# MCU_RTC_DIAGRAM_REV_2_0.net
KiCad netlist of a schematic drawn in EAGLE
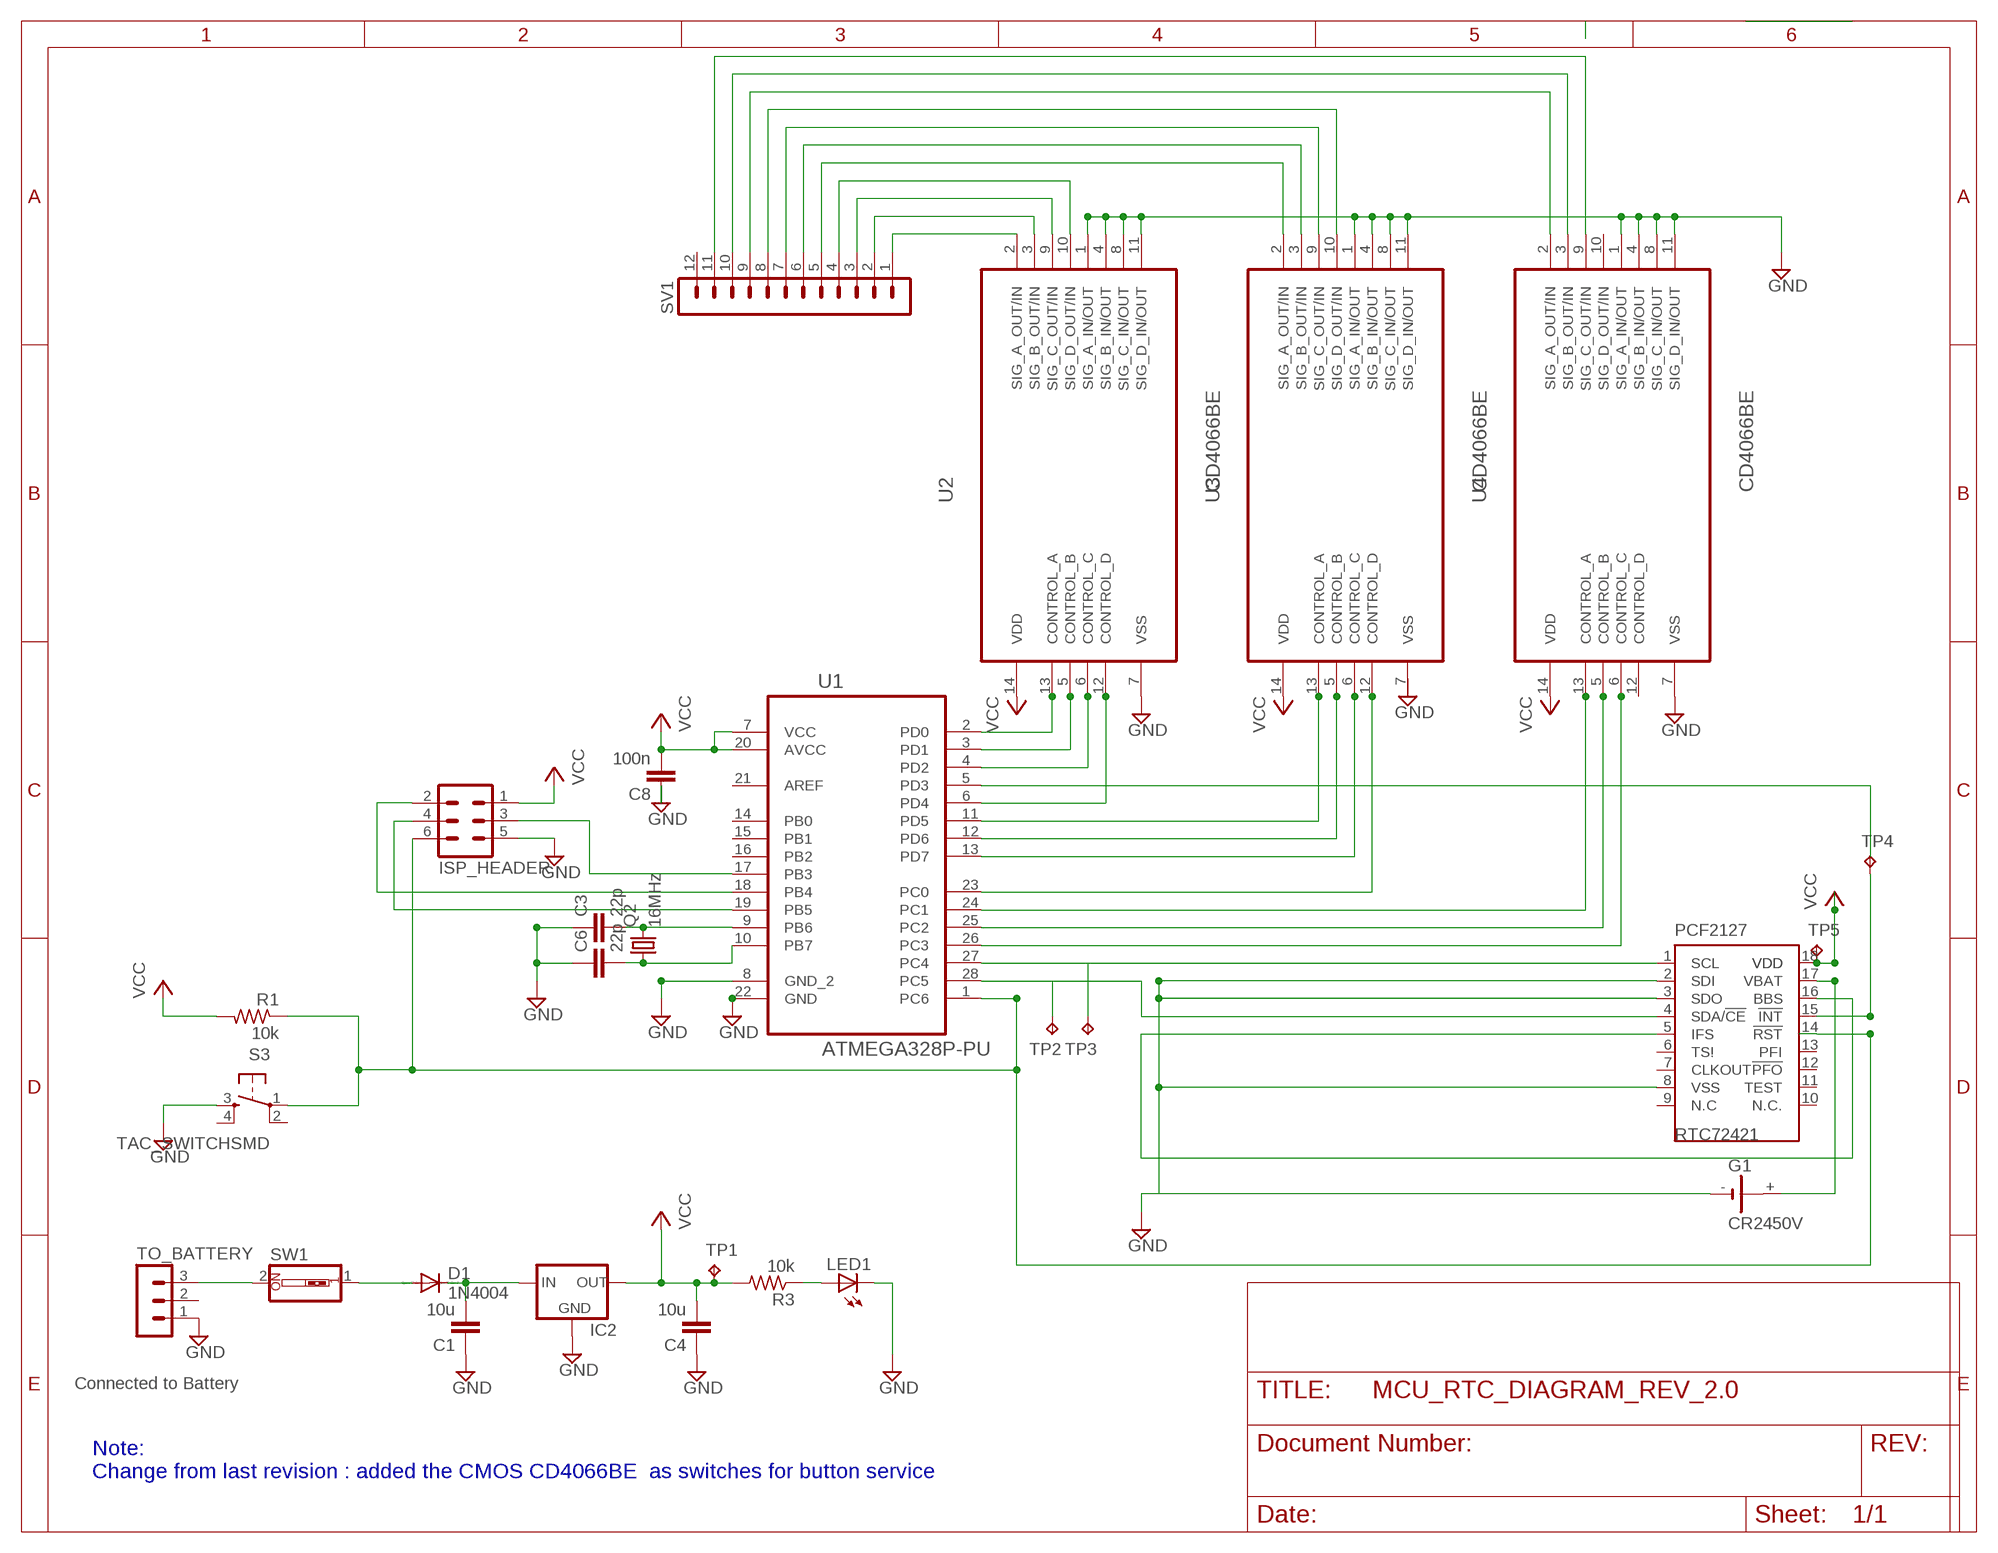
[diagram p0: schematic, sheet 1]

(export (version "E")
  (design (tool "Eeschema 10.0.6"))
  (components
    (comp (ref "C1")
      (value "10u")
      (footprint "eagle-import:C0805")
      (libsource (lib "eagle-import") (part "C-EUC0805"))
    )
    (comp (ref "C3")
      (value "22p")
      (footprint "eagle-import:C0805")
      (libsource (lib "eagle-import") (part "C-EUC0805"))
    )
    (comp (ref "C4")
      (value "10u")
      (footprint "eagle-import:C0805")
      (libsource (lib "eagle-import") (part "C-EUC0805"))
    )
    (comp (ref "C6")
      (value "22p")
      (footprint "eagle-import:C0805")
      (libsource (lib "eagle-import") (part "C-EUC0805"))
    )
    (comp (ref "C8")
      (value "100n")
      (footprint "eagle-import:C0805")
      (libsource (lib "eagle-import") (part "C-EUC0805"))
    )
    (comp (ref "D1")
      (value "1N4004")
      (footprint "eagle-import:DO41-10")
      (libsource (lib "eagle-import") (part "1N4004"))
    )
    (comp (ref "G1")
      (value "CR2450V")
      (footprint "eagle-import:CR2450V")
      (libsource (lib "eagle-import") (part "CR2450V"))
    )
    (comp (ref "IC1")
      (value "RTC72421")
      (footprint "eagle-import:DIL18")
      (fields (field (name "MPN") "RTC72421B"))
      (libsource (lib "eagle-import") (part "RTC72421"))
    )
    (comp (ref "IC2")
      (value "78XXL")
      (footprint "eagle-import:78XXL")
      (libsource (lib "eagle-import") (part "78XXL"))
    )
    (comp (ref "ISP_HEADER")
      (value "MA03-2")
      (footprint "eagle-import:MA03-2")
      (libsource (lib "eagle-import") (part "MA03-2"))
    )
    (comp (ref "LED1")
      (value "LEDCHIPLED_0805")
      (footprint "eagle-import:CHIPLED_0805")
      (libsource (lib "eagle-import") (part "LEDCHIPLED_0805"))
    )
    (comp (ref "Q2")
      (value "16MHz")
      (footprint "eagle-import:HC49_S")
      (libsource (lib "eagle-import") (part "CRYSTALHC49S"))
    )
    (comp (ref "R1")
      (value "10k")
      (footprint "eagle-import:R0805")
      (libsource (lib "eagle-import") (part "R-US_R0805"))
    )
    (comp (ref "R3")
      (value "10k")
      (footprint "eagle-import:R0805")
      (libsource (lib "eagle-import") (part "R-US_R0805"))
    )
    (comp (ref "S3")
      (value "TAC_SWITCHSMD")
      (footprint "eagle-import:TACTILE-SWITCH-SMD")
      (libsource (lib "eagle-import") (part "TAC_SWITCHSMD"))
    )
    (comp (ref "SV1")
      (value "MA12-1W")
      (footprint "eagle-import:MA12-1W")
      (libsource (lib "eagle-import") (part "MA12-1W"))
    )
    (comp (ref "SW1")
      (value "SW_DIP-1")
      (footprint "eagle-import:EDG-01")
      (libsource (lib "eagle-import") (part "SW_DIP-1"))
    )
    (comp (ref "TO_BATTERY")
      (value "MA03-1")
      (footprint "eagle-import:MA03-1")
      (libsource (lib "eagle-import") (part "MA03-1"))
    )
    (comp (ref "TP1")
      (value "TPB1,27")
      (footprint "eagle-import:B1,27")
      (libsource (lib "eagle-import") (part "TPB1,27"))
    )
    (comp (ref "TP2")
      (value "TPB1,27")
      (footprint "eagle-import:B1,27")
      (libsource (lib "eagle-import") (part "TPB1,27"))
    )
    (comp (ref "TP3")
      (value "TPB1,27")
      (footprint "eagle-import:B1,27")
      (libsource (lib "eagle-import") (part "TPB1,27"))
    )
    (comp (ref "TP4")
      (value "TPB1,27")
      (footprint "eagle-import:B1,27")
      (libsource (lib "eagle-import") (part "TPB1,27"))
    )
    (comp (ref "TP5")
      (value "TPB1,27")
      (footprint "eagle-import:B1,27")
      (libsource (lib "eagle-import") (part "TPB1,27"))
    )
    (comp (ref "U1")
      (value "ATMEGA328P-PU")
      (footprint "eagle-import:DIP254P762X457-28")
      (libsource (lib "eagle-import") (part "ATMEGA328P-PU"))
    )
    (comp (ref "U2")
      (value "CD4066BE")
      (footprint "eagle-import:DIP254P762X508-14")
      (libsource (lib "eagle-import") (part "CD4066BE"))
    )
    (comp (ref "U3")
      (value "CD4066BE")
      (footprint "eagle-import:DIP254P762X508-14")
      (libsource (lib "eagle-import") (part "CD4066BE"))
    )
    (comp (ref "U4")
      (value "CD4066BE")
      (footprint "eagle-import:DIP254P762X508-14")
      (libsource (lib "eagle-import") (part "CD4066BE"))
    )
  )
  (nets
    (net (code "1") (name "GND") (class "Default")
      (node (ref "C1") (pin "1") (pinfunction "1_1") (pintype "passive"))
      (node (ref "C3") (pin "1") (pinfunction "1_1") (pintype "passive"))
      (node (ref "C4") (pin "1") (pinfunction "1_1") (pintype "passive"))
      (node (ref "C6") (pin "1") (pinfunction "1_1") (pintype "passive"))
      (node (ref "C8") (pin "1") (pinfunction "1_1") (pintype "passive"))
      (node (ref "G1") (pin "-") (pinfunction "-_-") (pintype "passive"))
      (node (ref "IC1") (pin "2") (pinfunction "SDI_2") (pintype "input"))
      (node (ref "IC1") (pin "3") (pinfunction "SDO_3") (pintype "input"))
      (node (ref "IC1") (pin "8") (pinfunction "VSS_8") (pintype "input"))
      (node (ref "IC2") (pin "GND") (pinfunction "GND_GND") (pintype "input"))
      (node (ref "ISP_HEADER") (pin "5") (pinfunction "5_5") (pintype "passive"))
      (node (ref "LED1") (pin "C") (pinfunction "C_C") (pintype "passive"))
      (node (ref "S3") (pin "3") (pinfunction "3_3") (pintype "passive"))
      (node (ref "TO_BATTERY") (pin "1") (pinfunction "1_1") (pintype "passive"))
      (node (ref "U1") (pin "22") (pinfunction "GND_22") (pintype "passive"))
      (node (ref "U1") (pin "8") (pinfunction "GND_2_8") (pintype "passive"))
      (node (ref "U2") (pin "1") (pinfunction "SIG_A_IN/OUT_1") (pintype "bidirectional"))
      (node (ref "U2") (pin "11") (pinfunction "SIG_D_IN/OUT_11") (pintype "bidirectional"))
      (node (ref "U2") (pin "4") (pinfunction "SIG_B_IN/OUT_4") (pintype "bidirectional"))
      (node (ref "U2") (pin "7") (pinfunction "VSS_7") (pintype "passive"))
      (node (ref "U2") (pin "8") (pinfunction "SIG_C_IN/OUT_8") (pintype "bidirectional"))
      (node (ref "U3") (pin "1") (pinfunction "SIG_A_IN/OUT_1") (pintype "bidirectional"))
      (node (ref "U3") (pin "11") (pinfunction "SIG_D_IN/OUT_11") (pintype "bidirectional"))
      (node (ref "U3") (pin "4") (pinfunction "SIG_B_IN/OUT_4") (pintype "bidirectional"))
      (node (ref "U3") (pin "8") (pinfunction "SIG_C_IN/OUT_8") (pintype "bidirectional"))
      (node (ref "U4") (pin "1") (pinfunction "SIG_A_IN/OUT_1") (pintype "bidirectional"))
      (node (ref "U4") (pin "11") (pinfunction "SIG_D_IN/OUT_11") (pintype "bidirectional"))
      (node (ref "U4") (pin "4") (pinfunction "SIG_B_IN/OUT_4") (pintype "bidirectional"))
      (node (ref "U4") (pin "7") (pinfunction "VSS_7") (pintype "passive"))
      (node (ref "U4") (pin "8") (pinfunction "SIG_C_IN/OUT_8") (pintype "bidirectional"))
    )
    (net (code "2") (name "Net-(C1-Pad2)") (class "Default")
      (node (ref "C1") (pin "2") (pinfunction "2_2") (pintype "passive"))
      (node (ref "D1") (pin "C") (pinfunction "C_C") (pintype "passive"))
      (node (ref "IC2") (pin "IN") (pinfunction "IN_IN") (pintype "input"))
    )
    (net (code "3") (name "Net-(D1-PadA)") (class "Default")
      (node (ref "D1") (pin "A") (pinfunction "A_A") (pintype "passive"))
      (node (ref "SW1") (pin "1") (pinfunction "1_1") (pintype "passive"))
    )
    (net (code "4") (name "Net-(IC1-IFS)") (class "Default")
      (node (ref "IC1") (pin "16") (pinfunction "VCC_16") (pintype "power_in"))
      (node (ref "IC1") (pin "5") (pinfunction "IFS_5") (pintype "input"))
    )
    (net (code "5") (name "Net-(IC1-SCL)") (class "Default")
      (node (ref "IC1") (pin "1") (pinfunction "SCL_1") (pintype "input"))
      (node (ref "TP3") (pin "TP") (pinfunction "TP_TP") (pintype "input"))
      (node (ref "U1") (pin "27") (pinfunction "PC4_27") (pintype "bidirectional"))
    )
    (net (code "6") (name "Net-(IC1-SDA{slash}~{CE})") (class "Default")
      (node (ref "IC1") (pin "4") (pinfunction "SDA/~{CE}_4") (pintype "input"))
      (node (ref "TP2") (pin "TP") (pinfunction "TP_TP") (pintype "input"))
      (node (ref "U1") (pin "28") (pinfunction "PC5_28") (pintype "bidirectional"))
    )
    (net (code "7") (name "Net-(IC1-VBAT)") (class "Default")
      (node (ref "G1") (pin "+") (pinfunction "+_+") (pintype "passive"))
      (node (ref "IC1") (pin "17") (pinfunction "VBAT_17") (pintype "power_in"))
    )
    (net (code "8") (name "Net-(IC1-~{INT})") (class "Default")
      (node (ref "IC1") (pin "15") (pinfunction "~{INT}_15") (pintype "input"))
      (node (ref "TP4") (pin "TP") (pinfunction "TP_TP") (pintype "input"))
    )
    (net (code "9") (name "Net-(IC1-~{RST})") (class "Default")
      (node (ref "IC1") (pin "14") (pinfunction "~{RST}_14") (pintype "bidirectional"))
      (node (ref "ISP_HEADER") (pin "6") (pinfunction "6_6") (pintype "passive"))
      (node (ref "R1") (pin "1") (pinfunction "1_1") (pintype "passive"))
      (node (ref "S3") (pin "1") (pinfunction "1_1") (pintype "passive"))
      (node (ref "U1") (pin "1") (pinfunction "PC6_1") (pintype "bidirectional"))
    )
    (net (code "10") (name "Net-(LED1-PadA)") (class "Default")
      (node (ref "LED1") (pin "A") (pinfunction "A_A") (pintype "passive"))
      (node (ref "R3") (pin "1") (pinfunction "1_1") (pintype "passive"))
    )
    (net (code "11") (name "Net-(SW1-Pad2)") (class "Default")
      (node (ref "SW1") (pin "2") (pinfunction "2_2") (pintype "passive"))
      (node (ref "TO_BATTERY") (pin "3") (pinfunction "3_3") (pintype "passive"))
    )
    (net (code "12") (name "Net-(U1-PB3)") (class "Default")
      (node (ref "ISP_HEADER") (pin "3") (pinfunction "3_3") (pintype "passive"))
      (node (ref "U1") (pin "17") (pinfunction "PB3_17") (pintype "bidirectional"))
    )
    (net (code "13") (name "Net-(U1-PB4)") (class "Default")
      (node (ref "ISP_HEADER") (pin "2") (pinfunction "2_2") (pintype "passive"))
      (node (ref "U1") (pin "18") (pinfunction "PB4_18") (pintype "bidirectional"))
    )
    (net (code "14") (name "Net-(U1-PB5)") (class "Default")
      (node (ref "ISP_HEADER") (pin "4") (pinfunction "4_4") (pintype "passive"))
      (node (ref "U1") (pin "19") (pinfunction "PB5_19") (pintype "bidirectional"))
    )
    (net (code "15") (name "Net-(U1-PB6)") (class "Default")
      (node (ref "C3") (pin "2") (pinfunction "2_2") (pintype "passive"))
      (node (ref "Q2") (pin "2") (pinfunction "2_2") (pintype "passive"))
      (node (ref "U1") (pin "9") (pinfunction "PB6_9") (pintype "bidirectional"))
    )
    (net (code "16") (name "Net-(U1-PB7)") (class "Default")
      (node (ref "C6") (pin "2") (pinfunction "2_2") (pintype "passive"))
      (node (ref "Q2") (pin "1") (pinfunction "1_1") (pintype "passive"))
      (node (ref "U1") (pin "10") (pinfunction "PB7_10") (pintype "bidirectional"))
    )
    (net (code "17") (name "Net-(U1-PC0)") (class "Default")
      (node (ref "U1") (pin "23") (pinfunction "PC0_23") (pintype "bidirectional"))
      (node (ref "U3") (pin "12") (pinfunction "CONTROL_D_12") (pintype "input"))
    )
    (net (code "18") (name "Net-(U1-PC1)") (class "Default")
      (node (ref "U1") (pin "24") (pinfunction "PC1_24") (pintype "bidirectional"))
      (node (ref "U4") (pin "13") (pinfunction "CONTROL_A_13") (pintype "input"))
    )
    (net (code "19") (name "Net-(U1-PC2)") (class "Default")
      (node (ref "U1") (pin "25") (pinfunction "PC2_25") (pintype "bidirectional"))
      (node (ref "U4") (pin "5") (pinfunction "CONTROL_B_5") (pintype "input"))
    )
    (net (code "20") (name "Net-(U1-PC3)") (class "Default")
      (node (ref "U1") (pin "26") (pinfunction "PC3_26") (pintype "bidirectional"))
      (node (ref "U4") (pin "6") (pinfunction "CONTROL_C_6") (pintype "input"))
    )
    (net (code "21") (name "Net-(U1-PD0)") (class "Default")
      (node (ref "U1") (pin "2") (pinfunction "PD0_2") (pintype "bidirectional"))
      (node (ref "U2") (pin "13") (pinfunction "CONTROL_A_13") (pintype "input"))
    )
    (net (code "22") (name "Net-(U1-PD1)") (class "Default")
      (node (ref "U1") (pin "3") (pinfunction "PD1_3") (pintype "bidirectional"))
      (node (ref "U2") (pin "5") (pinfunction "CONTROL_B_5") (pintype "input"))
    )
    (net (code "23") (name "Net-(U1-PD2)") (class "Default")
      (node (ref "U1") (pin "4") (pinfunction "PD2_4") (pintype "bidirectional"))
      (node (ref "U2") (pin "6") (pinfunction "CONTROL_C_6") (pintype "input"))
    )
    (net (code "24") (name "Net-(U1-PD4)") (class "Default")
      (node (ref "U1") (pin "6") (pinfunction "PD4_6") (pintype "bidirectional"))
      (node (ref "U2") (pin "12") (pinfunction "CONTROL_D_12") (pintype "input"))
    )
    (net (code "25") (name "Net-(U1-PD5)") (class "Default")
      (node (ref "U1") (pin "11") (pinfunction "PD5_11") (pintype "bidirectional"))
      (node (ref "U3") (pin "13") (pinfunction "CONTROL_A_13") (pintype "input"))
    )
    (net (code "26") (name "Net-(U1-PD6)") (class "Default")
      (node (ref "U1") (pin "12") (pinfunction "PD6_12") (pintype "bidirectional"))
      (node (ref "U3") (pin "5") (pinfunction "CONTROL_B_5") (pintype "input"))
    )
    (net (code "27") (name "Net-(U1-PD7)") (class "Default")
      (node (ref "U1") (pin "13") (pinfunction "PD7_13") (pintype "bidirectional"))
      (node (ref "U3") (pin "6") (pinfunction "CONTROL_C_6") (pintype "input"))
    )
    (net (code "28") (name "Net-(U2-SIG_A_OUT{slash}IN)") (class "Default")
      (node (ref "SV1") (pin "1") (pinfunction "1_1") (pintype "passive"))
      (node (ref "U2") (pin "2") (pinfunction "SIG_A_OUT/IN_2") (pintype "bidirectional"))
    )
    (net (code "29") (name "Net-(U2-SIG_B_OUT{slash}IN)") (class "Default")
      (node (ref "SV1") (pin "2") (pinfunction "2_2") (pintype "passive"))
      (node (ref "U2") (pin "3") (pinfunction "SIG_B_OUT/IN_3") (pintype "bidirectional"))
    )
    (net (code "30") (name "Net-(U2-SIG_C_OUT{slash}IN)") (class "Default")
      (node (ref "SV1") (pin "3") (pinfunction "3_3") (pintype "passive"))
      (node (ref "U2") (pin "9") (pinfunction "SIG_C_OUT/IN_9") (pintype "bidirectional"))
    )
    (net (code "31") (name "Net-(U2-SIG_D_OUT{slash}IN)") (class "Default")
      (node (ref "SV1") (pin "4") (pinfunction "4_4") (pintype "passive"))
      (node (ref "U2") (pin "10") (pinfunction "SIG_D_OUT/IN_10") (pintype "bidirectional"))
    )
    (net (code "32") (name "Net-(U3-SIG_A_OUT{slash}IN)") (class "Default")
      (node (ref "SV1") (pin "5") (pinfunction "5_5") (pintype "passive"))
      (node (ref "U3") (pin "2") (pinfunction "SIG_A_OUT/IN_2") (pintype "bidirectional"))
    )
    (net (code "33") (name "Net-(U3-SIG_B_OUT{slash}IN)") (class "Default")
      (node (ref "SV1") (pin "6") (pinfunction "6_6") (pintype "passive"))
      (node (ref "U3") (pin "3") (pinfunction "SIG_B_OUT/IN_3") (pintype "bidirectional"))
    )
    (net (code "34") (name "Net-(U3-SIG_C_OUT{slash}IN)") (class "Default")
      (node (ref "SV1") (pin "7") (pinfunction "7_7") (pintype "passive"))
      (node (ref "U3") (pin "9") (pinfunction "SIG_C_OUT/IN_9") (pintype "bidirectional"))
    )
    (net (code "35") (name "Net-(U3-SIG_D_OUT{slash}IN)") (class "Default")
      (node (ref "SV1") (pin "8") (pinfunction "8_8") (pintype "passive"))
      (node (ref "U3") (pin "10") (pinfunction "SIG_D_OUT/IN_10") (pintype "bidirectional"))
    )
    (net (code "36") (name "Net-(U4-SIG_A_OUT{slash}IN)") (class "Default")
      (node (ref "SV1") (pin "9") (pinfunction "9_9") (pintype "passive"))
      (node (ref "U4") (pin "2") (pinfunction "SIG_A_OUT/IN_2") (pintype "bidirectional"))
    )
    (net (code "37") (name "Net-(U4-SIG_B_OUT{slash}IN)") (class "Default")
      (node (ref "SV1") (pin "10") (pinfunction "10_10") (pintype "passive"))
      (node (ref "U4") (pin "3") (pinfunction "SIG_B_OUT/IN_3") (pintype "bidirectional"))
    )
    (net (code "38") (name "Net-(U4-SIG_C_OUT{slash}IN)") (class "Default")
      (node (ref "SV1") (pin "11") (pinfunction "11_11") (pintype "passive"))
      (node (ref "U4") (pin "9") (pinfunction "SIG_C_OUT/IN_9") (pintype "bidirectional"))
    )
    (net (code "39") (name "VCC") (class "Default")
      (node (ref "C4") (pin "2") (pinfunction "2_2") (pintype "passive"))
      (node (ref "C8") (pin "2") (pinfunction "2_2") (pintype "passive"))
      (node (ref "IC1") (pin "18") (pinfunction "VDD_18") (pintype "power_in"))
      (node (ref "IC2") (pin "OUT") (pinfunction "OUT_OUT") (pintype "passive"))
      (node (ref "ISP_HEADER") (pin "1") (pinfunction "1_1") (pintype "passive"))
      (node (ref "R1") (pin "2") (pinfunction "2_2") (pintype "passive"))
      (node (ref "R3") (pin "2") (pinfunction "2_2") (pintype "passive"))
      (node (ref "TP1") (pin "TP") (pinfunction "TP_TP") (pintype "input"))
      (node (ref "TP5") (pin "TP") (pinfunction "TP_TP") (pintype "input"))
      (node (ref "U1") (pin "20") (pinfunction "AVCC_20") (pintype "power_in"))
      (node (ref "U1") (pin "7") (pinfunction "VCC_7") (pintype "power_in"))
      (node (ref "U2") (pin "14") (pinfunction "VDD_14") (pintype "power_in"))
      (node (ref "U3") (pin "14") (pinfunction "VDD_14") (pintype "power_in"))
      (node (ref "U4") (pin "14") (pinfunction "VDD_14") (pintype "power_in"))
    )
    (net (code "40") (name "unconnected-(G1-+-Pad+@1)") (class "Default")
      (node (ref "G1") (pin "+@1") (pinfunction "+_+@1") (pintype "passive"))
    )
    (net (code "41") (name "unconnected-(IC1-CLKOUT-Pad7)") (class "Default")
      (node (ref "IC1") (pin "7") (pinfunction "CLKOUT_7") (pintype "input"))
    )
    (net (code "42") (name "unconnected-(IC1-N.C-Pad9)") (class "Default")
      (node (ref "IC1") (pin "9") (pinfunction "N.C_9") (pintype "input"))
    )
    (net (code "43") (name "unconnected-(IC1-N.C.-Pad10)") (class "Default")
      (node (ref "IC1") (pin "10") (pinfunction "N.C._10") (pintype "input"))
    )
    (net (code "44") (name "unconnected-(IC1-PFI-Pad13)") (class "Default")
      (node (ref "IC1") (pin "13") (pinfunction "PFI_13") (pintype "bidirectional"))
    )
    (net (code "45") (name "unconnected-(IC1-TEST-Pad11)") (class "Default")
      (node (ref "IC1") (pin "11") (pinfunction "TEST_11") (pintype "bidirectional"))
    )
    (net (code "46") (name "unconnected-(IC1-TS~{}-Pad6)") (class "Default")
      (node (ref "IC1") (pin "6") (pinfunction "TS~{}_6") (pintype "input"))
    )
    (net (code "47") (name "unconnected-(IC1-~{PFO}-Pad12)") (class "Default")
      (node (ref "IC1") (pin "12") (pinfunction "~{PFO}_12") (pintype "bidirectional"))
    )
    (net (code "48") (name "unconnected-(S3-Pad2)") (class "Default")
      (node (ref "S3") (pin "2") (pinfunction "2_2") (pintype "passive"))
    )
    (net (code "49") (name "unconnected-(S3-Pad4)") (class "Default")
      (node (ref "S3") (pin "4") (pinfunction "4_4") (pintype "passive"))
    )
    (net (code "50") (name "unconnected-(SV1-Pad12)") (class "Default")
      (node (ref "SV1") (pin "12") (pinfunction "12_12") (pintype "passive"))
    )
    (net (code "51") (name "unconnected-(TO_BATTERY-Pad2)") (class "Default")
      (node (ref "TO_BATTERY") (pin "2") (pinfunction "2_2") (pintype "passive"))
    )
    (net (code "52") (name "unconnected-(U1-AREF-Pad21)") (class "Default")
      (node (ref "U1") (pin "21") (pinfunction "AREF_21") (pintype "input"))
    )
    (net (code "53") (name "unconnected-(U1-PB0-Pad14)") (class "Default")
      (node (ref "U1") (pin "14") (pinfunction "PB0_14") (pintype "bidirectional"))
    )
    (net (code "54") (name "unconnected-(U1-PB1-Pad15)") (class "Default")
      (node (ref "U1") (pin "15") (pinfunction "PB1_15") (pintype "bidirectional"))
    )
    (net (code "55") (name "unconnected-(U1-PB2-Pad16)") (class "Default")
      (node (ref "U1") (pin "16") (pinfunction "PB2_16") (pintype "bidirectional"))
    )
    (net (code "56") (name "unconnected-(U1-PD3-Pad5)") (class "Default")
      (node (ref "U1") (pin "5") (pinfunction "PD3_5") (pintype "bidirectional"))
    )
    (net (code "57") (name "unconnected-(U3-VSS-Pad7)") (class "Default")
      (node (ref "U3") (pin "7") (pinfunction "VSS_7") (pintype "passive"))
    )
    (net (code "58") (name "unconnected-(U4-CONTROL_D-Pad12)") (class "Default")
      (node (ref "U4") (pin "12") (pinfunction "CONTROL_D_12") (pintype "input"))
    )
    (net (code "59") (name "unconnected-(U4-SIG_D_OUT{slash}IN-Pad10)") (class "Default")
      (node (ref "U4") (pin "10") (pinfunction "SIG_D_OUT/IN_10") (pintype "bidirectional"))
    )
  )
)
